# power_conversion.net
KiCad netlist of a schematic drawn in Altium Designer
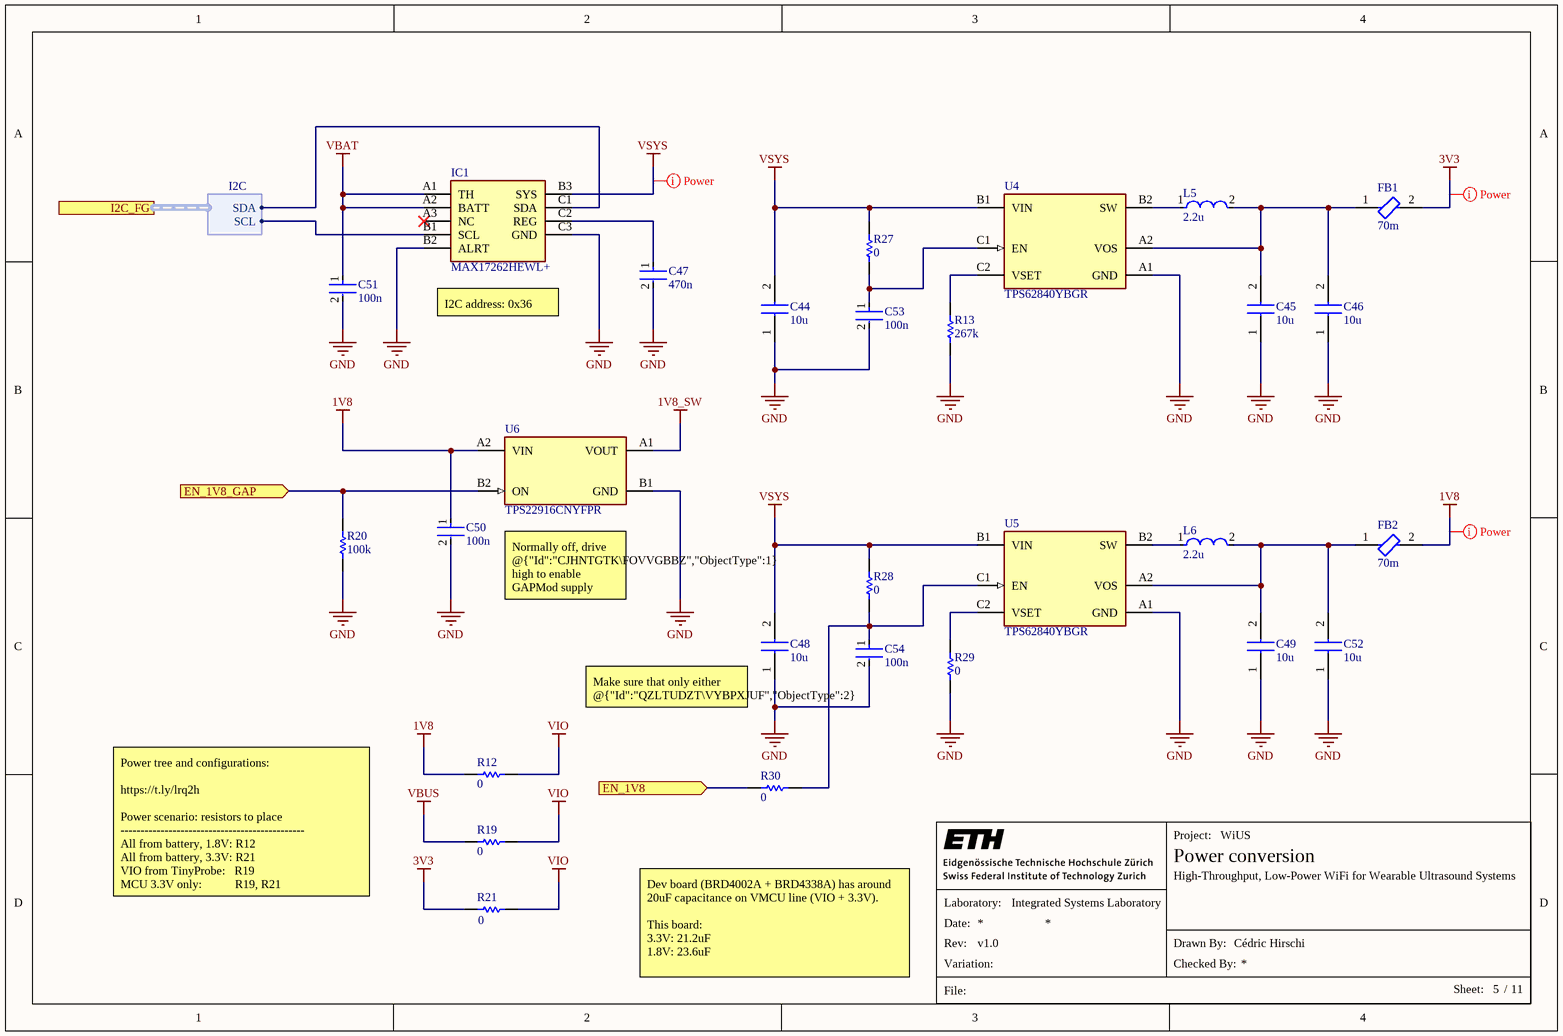
[diagram p0: power_conversion.SchDoc]

(export (version "E")
  (design (tool "Eeschema 10.0.6"))
  (components
    (comp (ref "C44")
      (value "10u")
      (footprint "SamacSys:CAPC1608X100N")
      (description "Cap Cer 10UF 10V X7R 0603")
      (fields (field (name "MANUFACTURER_PART_NUMBER") "GMC10X7R106K10NT"))
      (libsource (lib "*") (part "GMC10X7R106K10NT"))
    )
    (comp (ref "C45")
      (value "10u")
      (footprint "SamacSys:CAPC1608X100N")
      (description "Cap Cer 10UF 10V X7R 0603")
      (fields (field (name "MANUFACTURER_PART_NUMBER") "GMC10X7R106K10NT"))
      (libsource (lib "*") (part "GMC10X7R106K10NT"))
    )
    (comp (ref "C46")
      (value "10u")
      (footprint "SamacSys:CAPC1608X100N")
      (description "Cap Cer 10UF 10V X7R 0603")
      (fields (field (name "MANUFACTURER_PART_NUMBER") "GMC10X7R106K10NT"))
      (libsource (lib "*") (part "GMC10X7R106K10NT"))
    )
    (comp (ref "C47")
      (value "470n")
      (footprint "FP-GRM15-0_1-MFG")
      (description "CAP CER 0.47UF 10V X5R 0402")
      (fields
        (field (name "MANUFACTURER") "Murata Electronics North America")
        (field (name "MANUFACTURER PART NUMBER") "GRM155R61A474KE15D")
      )
      (libsource (lib "Altium Content Vault") (part "11868f565c42a9108669ba33697ecf6"))
    )
    (comp (ref "C48")
      (value "10u")
      (footprint "SamacSys:CAPC1608X100N")
      (description "Cap Cer 10UF 10V X7R 0603")
      (fields (field (name "MANUFACTURER_PART_NUMBER") "GMC10X7R106K10NT"))
      (libsource (lib "*") (part "GMC10X7R106K10NT"))
    )
    (comp (ref "C49")
      (value "10u")
      (footprint "SamacSys:CAPC1608X100N")
      (description "Cap Cer 10UF 10V X7R 0603")
      (fields (field (name "MANUFACTURER_PART_NUMBER") "GMC10X7R106K10NT"))
      (libsource (lib "*") (part "GMC10X7R106K10NT"))
    )
    (comp (ref "C50")
      (value "100n")
      (footprint "FP-GRT155-0_05-MFG")
      (description "Multi-Layer Ceramic Capacitor 100nF 50V X7R ±10% 0402 Paper T/R")
      (libsource (lib "Altium Content Vault") (part "02cd4be3c70576c341d710602a673aa"))
    )
    (comp (ref "C51")
      (value "100n")
      (footprint "FP-GRT155-0_05-MFG")
      (description "Multi-Layer Ceramic Capacitor 100nF 50V X7R ±10% 0402 Paper T/R")
      (libsource (lib "Altium Content Vault") (part "02cd4be3c70576c341d710602a673aa"))
    )
    (comp (ref "C52")
      (value "10u")
      (footprint "SamacSys:CAPC1608X100N")
      (description "Cap Cer 10UF 10V X7R 0603")
      (fields (field (name "MANUFACTURER_PART_NUMBER") "GMC10X7R106K10NT"))
      (libsource (lib "*") (part "GMC10X7R106K10NT"))
    )
    (comp (ref "C53")
      (value "100n")
      (footprint "FP-GRT155-0_05-MFG")
      (description "Multi-Layer Ceramic Capacitor 100nF 50V X7R ±10% 0402 Paper T/R")
      (libsource (lib "Altium Content Vault") (part "02cd4be3c70576c341d710602a673aa"))
    )
    (comp (ref "C54")
      (value "100n")
      (footprint "FP-GRT155-0_05-MFG")
      (description "Multi-Layer Ceramic Capacitor 100nF 50V X7R ±10% 0402 Paper T/R")
      (libsource (lib "Altium Content Vault") (part "02cd4be3c70576c341d710602a673aa"))
    )
    (comp (ref "FB1")
      (value "70m")
      (footprint "FP-BLM15-0_05-MFG")
      (description "Chip Ferrite Bead, 0402, 80Ω @ 100MHz, 0.07Ω, 25%, 1.5A")
      (fields (field (name "TOLERANCE") "25%"))
      (libsource (lib "Altium Content Vault") (part "5f30dd21d616792df468990f7003faa"))
    )
    (comp (ref "FB2")
      (value "70m")
      (footprint "FP-BLM15-0_05-MFG")
      (description "Chip Ferrite Bead, 0402, 80Ω @ 100MHz, 0.07Ω, 25%, 1.5A")
      (fields (field (name "TOLERANCE") "25%"))
      (libsource (lib "Altium Content Vault") (part "5f30dd21d616792df468990f7003faa"))
    )
    (comp (ref "IC1")
      (value "MAX17262HEWL+")
      (footprint "wius:BGA9C40P3X3_153X153X69")
      (description "Integrated Circuit")
      (libsource (lib "wius") (part "MAX17262HEWL+"))
    )
    (comp (ref "L5")
      (value "2.2u")
      (footprint "FP-DFE201612C-MFG")
      (description "Shielded Wirewound Inductor 2.2uH 20% 1800mA 0.116Ω 0806 (2016)")
      (libsource (lib "Altium Content Vault") (part "725321dda6339637d4d059423bc1c3c"))
    )
    (comp (ref "L6")
      (value "2.2u")
      (footprint "FP-DFE201612C-MFG")
      (description "Shielded Wirewound Inductor 2.2uH 20% 1800mA 0.116Ω 0806 (2016)")
      (libsource (lib "Altium Content Vault") (part "725321dda6339637d4d059423bc1c3c"))
    )
    (comp (ref "R12")
      (value "0")
      (footprint "RESC1005X40X25ML05T10")
      (description "Chip Resistor, 0 Ohm, 0.063 W, -55 to 155 degC, 0402 (1005 Metric)")
      (fields (field (name "POWER") "63mW") (field (name "Comment") "Resistor 0R 0402 63 mW"))
      (libsource (lib "Cédric's Workspace") (part "RES-2"))
    )
    (comp (ref "R13")
      (value "267k")
      (footprint "RESC1005X40X25LL05T10")
      (fields (field (name "MANUFACTURER") "Yageo") (field (name "PART NUMBER") "RC0402FR-07267KL"))
      (libsource (lib "Altium Content Vault") (part "RES"))
    )
    (comp (ref "R19")
      (value "0")
      (footprint "RESC1005X40X25ML05T10")
      (description "Chip Resistor, 0 Ohm, 0.063 W, -55 to 155 degC, 0402 (1005 Metric)")
      (fields (field (name "POWER") "63mW") (field (name "Comment") "Resistor 0R 0402 63 mW"))
      (libsource (lib "Cédric's Workspace") (part "RES-2"))
    )
    (comp (ref "R20")
      (value "100k")
      (footprint "RESC1005X40X25NL05T10")
      (fields (field (name "PART NUMBER") "RC0402FR-07100KL") (field (name "MANUFACTURER") "Yageo / Phycomp"))
      (libsource (lib "Altium Content Vault") (part "RES"))
    )
    (comp (ref "R21")
      (value "0")
      (footprint "RESC1005X40X25ML05T10")
      (description "Chip Resistor, 0 Ohm, 0.063 W, -55 to 155 degC, 0402 (1005 Metric)")
      (fields (field (name "POWER") "63mW") (field (name "Comment") "Resistor 0R 0402 63 mW"))
      (libsource (lib "Cédric's Workspace") (part "RES-2"))
    )
    (comp (ref "R27")
      (value "0")
      (footprint "RESC1005X40X25ML05T10")
      (description "Chip Resistor, 0 Ohm, 0.063 W, -55 to 155 degC, 0402 (1005 Metric)")
      (fields (field (name "POWER") "63mW") (field (name "Comment") "Resistor 0R 0402 63 mW"))
      (libsource (lib "Cédric's Workspace") (part "RES-2"))
    )
    (comp (ref "R28")
      (value "0")
      (footprint "RESC1005X40X25ML05T10")
      (description "Chip Resistor, 0 Ohm, 0.063 W, -55 to 155 degC, 0402 (1005 Metric)")
      (fields (field (name "POWER") "63mW") (field (name "Comment") "Resistor 0R 0402 63 mW"))
      (libsource (lib "Cédric's Workspace") (part "RES-2"))
    )
    (comp (ref "R29")
      (value "0")
      (footprint "RESC1005X40X25ML05T10")
      (description "Chip Resistor, 0 Ohm, 0.063 W, -55 to 155 degC, 0402 (1005 Metric)")
      (fields (field (name "POWER") "63mW") (field (name "Comment") "Resistor 0R 0402 63 mW"))
      (libsource (lib "Cédric's Workspace") (part "RES-2"))
    )
    (comp (ref "R30")
      (value "0")
      (footprint "RESC1005X40X25ML05T10")
      (description "Chip Resistor, 0 Ohm, 0.063 W, -55 to 155 degC, 0402 (1005 Metric)")
      (fields (field (name "POWER") "63mW") (field (name "Comment") "Resistor 0R 0402 63 mW"))
      (libsource (lib "Cédric's Workspace") (part "RES-2"))
    )
    (comp (ref "U4")
      (value "TPS62840YBGR")
      (footprint "FP-YBG0006-MFG")
      (description "ULTRA LOW IQ BUCK CONVERTER")
      (libsource (lib "Altium Content Vault") (part "c4b2ba52c5c06523be8e235897d707d"))
    )
    (comp (ref "U5")
      (value "TPS62840YBGR")
      (footprint "FP-YBG0006-MFG")
      (description "ULTRA LOW IQ BUCK CONVERTER")
      (libsource (lib "Altium Content Vault") (part "c4b2ba52c5c06523be8e235897d707d"))
    )
    (comp (ref "U6")
      (value "TPS22916CNYFPR")
      (footprint "FP-YFP0004-IPC_C")
      (description "IC PWR SWITCH P-CHAN 1:1 4DSBGA")
      (libsource (lib "Altium Content Vault") (part "1899b175ee913ee136282ba2e26d23c"))
    )
  )
  (nets
    (net (code "2") (name "/EN_1V8") (class "Default")
      (node (ref "R30") (pin "1") (pinfunction "1_1") (pintype "passive"))
    )
    (net (code "3") (name "/EN_1V8_GAP") (class "Default")
      (node (ref "R20") (pin "2") (pinfunction "2_2") (pintype "passive"))
      (node (ref "U6") (pin "B2") (pinfunction "ON_B2") (pintype "input"))
    )
    (net (code "4") (name "/SCL") (class "Default")
      (node (ref "IC1") (pin "B1") (pinfunction "SCL_B1") (pintype "passive"))
    )
    (net (code "5") (name "/SDA") (class "Default")
      (node (ref "IC1") (pin "C1") (pinfunction "SDA_C1") (pintype "passive"))
    )
    (net (code "7") (name "1V8") (class "Default")
      (node (ref "C50") (pin "1") (pinfunction "1_1") (pintype "passive"))
      (node (ref "FB2") (pin "2") (pinfunction "2_2") (pintype "passive"))
      (node (ref "R12") (pin "2") (pinfunction "2_2") (pintype "passive"))
      (node (ref "U6") (pin "A2") (pinfunction "VIN_A2") (pintype "power_in"))
    )
    (net (code "8") (name "1V8_SW") (class "Default")
      (node (ref "U6") (pin "A1") (pinfunction "VOUT_A1") (pintype "power_in"))
    )
    (net (code "9") (name "3V3") (class "Default")
      (node (ref "FB1") (pin "2") (pinfunction "2_2") (pintype "passive"))
      (node (ref "R21") (pin "1") (pinfunction "1_1") (pintype "passive"))
    )
    (net (code "10") (name "GND") (class "Default")
      (node (ref "C44") (pin "1") (pinfunction "1_1") (pintype "passive"))
      (node (ref "C45") (pin "1") (pinfunction "1_1") (pintype "passive"))
      (node (ref "C46") (pin "1") (pinfunction "1_1") (pintype "passive"))
      (node (ref "C47") (pin "2") (pinfunction "2_2") (pintype "passive"))
      (node (ref "C48") (pin "1") (pinfunction "1_1") (pintype "passive"))
      (node (ref "C49") (pin "1") (pinfunction "1_1") (pintype "passive"))
      (node (ref "C50") (pin "2") (pinfunction "2_2") (pintype "passive"))
      (node (ref "C51") (pin "2") (pinfunction "2_2") (pintype "passive"))
      (node (ref "C52") (pin "1") (pinfunction "1_1") (pintype "passive"))
      (node (ref "C53") (pin "2") (pinfunction "2_2") (pintype "passive"))
      (node (ref "C54") (pin "2") (pinfunction "2_2") (pintype "passive"))
      (node (ref "IC1") (pin "B2") (pinfunction "ALRT_B2") (pintype "passive"))
      (node (ref "IC1") (pin "C3") (pinfunction "GND_C3") (pintype "passive"))
      (node (ref "R13") (pin "1") (pinfunction "1_1") (pintype "passive"))
      (node (ref "R20") (pin "1") (pinfunction "1_1") (pintype "passive"))
      (node (ref "R29") (pin "2") (pinfunction "2_2") (pintype "passive"))
      (node (ref "U4") (pin "A1") (pinfunction "GND_A1") (pintype "power_in"))
      (node (ref "U5") (pin "A1") (pinfunction "GND_A1") (pintype "power_in"))
      (node (ref "U6") (pin "B1") (pinfunction "GND_B1") (pintype "power_in"))
    )
    (net (code "11") (name "Net-(IC1-REG)") (class "Default")
      (node (ref "C47") (pin "1") (pinfunction "1_1") (pintype "passive"))
      (node (ref "IC1") (pin "C2") (pinfunction "REG_C2") (pintype "passive"))
    )
    (net (code "12") (name "Net-(U4-EN)") (class "Default")
      (node (ref "C53") (pin "1") (pinfunction "1_1") (pintype "passive"))
      (node (ref "R27") (pin "2") (pinfunction "2_2") (pintype "passive"))
      (node (ref "U4") (pin "C1") (pinfunction "EN_C1") (pintype "input"))
    )
    (net (code "13") (name "Net-(U4-SW)") (class "Default")
      (node (ref "L5") (pin "1") (pinfunction "1_1") (pintype "passive"))
      (node (ref "U4") (pin "B2") (pinfunction "SW_B2") (pintype "power_in"))
    )
    (net (code "14") (name "Net-(U4-VOS)") (class "Default")
      (node (ref "C45") (pin "2") (pinfunction "2_2") (pintype "passive"))
      (node (ref "C46") (pin "2") (pinfunction "2_2") (pintype "passive"))
      (node (ref "FB1") (pin "1") (pinfunction "1_1") (pintype "passive"))
      (node (ref "L5") (pin "2") (pinfunction "2_2") (pintype "passive"))
      (node (ref "U4") (pin "A2") (pinfunction "VOS_A2") (pintype "power_in"))
    )
    (net (code "15") (name "Net-(U4-VSET)") (class "Default")
      (node (ref "R13") (pin "2") (pinfunction "2_2") (pintype "passive"))
      (node (ref "U4") (pin "C2") (pinfunction "VSET_C2") (pintype "power_in"))
    )
    (net (code "16") (name "Net-(U5-EN)") (class "Default")
      (node (ref "C54") (pin "1") (pinfunction "1_1") (pintype "passive"))
      (node (ref "R28") (pin "2") (pinfunction "2_2") (pintype "passive"))
      (node (ref "R30") (pin "2") (pinfunction "2_2") (pintype "passive"))
      (node (ref "U5") (pin "C1") (pinfunction "EN_C1") (pintype "input"))
    )
    (net (code "17") (name "Net-(U5-SW)") (class "Default")
      (node (ref "L6") (pin "1") (pinfunction "1_1") (pintype "passive"))
      (node (ref "U5") (pin "B2") (pinfunction "SW_B2") (pintype "power_in"))
    )
    (net (code "18") (name "Net-(U5-VOS)") (class "Default")
      (node (ref "C49") (pin "2") (pinfunction "2_2") (pintype "passive"))
      (node (ref "C52") (pin "2") (pinfunction "2_2") (pintype "passive"))
      (node (ref "FB2") (pin "1") (pinfunction "1_1") (pintype "passive"))
      (node (ref "L6") (pin "2") (pinfunction "2_2") (pintype "passive"))
      (node (ref "U5") (pin "A2") (pinfunction "VOS_A2") (pintype "power_in"))
    )
    (net (code "19") (name "Net-(U5-VSET)") (class "Default")
      (node (ref "R29") (pin "1") (pinfunction "1_1") (pintype "passive"))
      (node (ref "U5") (pin "C2") (pinfunction "VSET_C2") (pintype "power_in"))
    )
    (net (code "20") (name "VBAT") (class "Default")
      (node (ref "C51") (pin "1") (pinfunction "1_1") (pintype "passive"))
      (node (ref "IC1") (pin "A1") (pinfunction "TH_A1") (pintype "passive"))
      (node (ref "IC1") (pin "A2") (pinfunction "BATT_A2") (pintype "passive"))
    )
    (net (code "21") (name "VBUS") (class "Default")
      (node (ref "R19") (pin "2") (pinfunction "2_2") (pintype "passive"))
    )
    (net (code "22") (name "VIO") (class "Default")
      (node (ref "R12") (pin "1") (pinfunction "1_1") (pintype "passive"))
      (node (ref "R19") (pin "1") (pinfunction "1_1") (pintype "passive"))
      (node (ref "R21") (pin "2") (pinfunction "2_2") (pintype "passive"))
    )
    (net (code "23") (name "VSYS") (class "Default")
      (node (ref "C44") (pin "2") (pinfunction "2_2") (pintype "passive"))
      (node (ref "C48") (pin "2") (pinfunction "2_2") (pintype "passive"))
      (node (ref "IC1") (pin "B3") (pinfunction "SYS_B3") (pintype "passive"))
      (node (ref "R27") (pin "1") (pinfunction "1_1") (pintype "passive"))
      (node (ref "R28") (pin "1") (pinfunction "1_1") (pintype "passive"))
      (node (ref "U4") (pin "B1") (pinfunction "VIN_B1") (pintype "power_in"))
      (node (ref "U5") (pin "B1") (pinfunction "VIN_B1") (pintype "power_in"))
    )
    (net (code "24") (name "unconnected-(IC1-NC-PadA3)") (class "Default")
      (node (ref "IC1") (pin "A3") (pinfunction "NC_A3") (pintype "passive+no_connect"))
    )
  )
)
